# INA228.net
KiCad netlist of a schematic drawn in Altium Designer
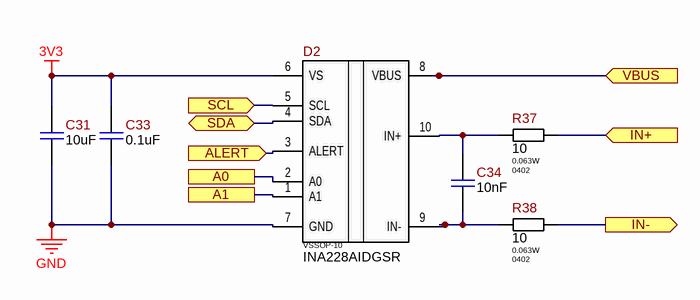
[diagram p0: INA228.SchDoc]

(export (version "E")
  (design (tool "Eeschema 10.0.6"))
  (components
    (comp (ref "C31")
      (value "10uF")
      (footprint "C0402(1005)")
      (description "CAP CER 10UF 6.3V X6S 0402")
      (fields (field (name "PART NUMBER") "10uF  6.3V C0402") (field (name "TOLERANCE") "±20%"))
      (libsource (lib "Database") (part "Capacitor_Ceramic"))
    )
    (comp (ref "C33")
      (value "0.1uF")
      (footprint "C0402(1005)")
      (description "CAP CER 0.1UF 25V X7R 0603")
      (fields (field (name "PART NUMBER") "0.1uF  25V C0403") (field (name "TOLERANCE") "±10%"))
      (libsource (lib "Database") (part "Capacitor_Ceramic"))
    )
    (comp (ref "C34")
      (value "10nF")
      (footprint "C0402(1005)")
      (description "CAP CER 10NF 50V NP0 0603")
      (fields (field (name "PART NUMBER") "10nF  50V C0402") (field (name "TOLERANCE") "±0.25pF"))
      (libsource (lib "Database") (part "Capacitor_Ceramic"))
    )
    (comp (ref "D2")
      (value "INA228AIDGSR")
      (footprint "TI-VSSOP-10-50P490X110")
      (description "85V, 20Bit, Ultra-Precise Power/Energy/Charge Monitor With I2C, 2.7V to 5.5V Supply, VSSOP-10")
      (fields
        (field (name "PACKAGE") "VSSOP-10")
        (field (name "PART NUMBER") "INA228AIDGSR")
        (field (name "MANUFACTURER") "Texas Instruments")
      )
      (libsource (lib "AjaxLibrary") (part "INA228AxDGS"))
    )
    (comp (ref "R37")
      (value "10")
      (footprint "R0402")
      (description "RES SMD 10 OHM  ±1% 1/16W 0402")
      (fields
        (field (name "POWER RATING") "0.063W")
        (field (name "PACKAGE/CASE") "0402")
        (field (name "PART NUMBER") "10  R0402")
        (field (name "TOLERANCE") "±1%")
      )
      (libsource (lib "Database") (part "R0402"))
    )
    (comp (ref "R38")
      (value "10")
      (footprint "R0402")
      (description "RES SMD 10 OHM  ±1% 1/16W 0402")
      (fields
        (field (name "POWER RATING") "0.063W")
        (field (name "PACKAGE/CASE") "0402")
        (field (name "PART NUMBER") "10  R0402")
        (field (name "TOLERANCE") "±1%")
      )
      (libsource (lib "Database") (part "R0402"))
    )
  )
  (nets
    (net (code "1") (name "/A0") (class "Default")
      (node (ref "D2") (pin "2") (pinfunction "A0_2") (pintype "passive"))
    )
    (net (code "2") (name "/A1") (class "Default")
      (node (ref "D2") (pin "1") (pinfunction "A1_1") (pintype "passive"))
    )
    (net (code "3") (name "/ALERT") (class "Default")
      (node (ref "D2") (pin "3") (pinfunction "ALERT_3") (pintype "passive"))
    )
    (net (code "4") (name "/IN+") (class "Default")
      (node (ref "R37") (pin "2") (pinfunction "2_2") (pintype "passive"))
    )
    (net (code "5") (name "/IN-") (class "Default")
      (node (ref "R38") (pin "2") (pinfunction "2_2") (pintype "passive"))
    )
    (net (code "6") (name "/SCL") (class "Default")
      (node (ref "D2") (pin "5") (pinfunction "SCL_5") (pintype "passive"))
    )
    (net (code "7") (name "/SDA") (class "Default")
      (node (ref "D2") (pin "4") (pinfunction "SDA_4") (pintype "passive"))
    )
    (net (code "8") (name "/VBUS") (class "Default")
      (node (ref "D2") (pin "8") (pinfunction "VBUS_8") (pintype "passive"))
    )
    (net (code "9") (name "3V3") (class "Default")
      (node (ref "C31") (pin "2") (pinfunction "2_2") (pintype "passive"))
      (node (ref "C33") (pin "2") (pinfunction "2_2") (pintype "passive"))
      (node (ref "D2") (pin "6") (pinfunction "VS_6") (pintype "passive"))
    )
    (net (code "10") (name "GND") (class "Default")
      (node (ref "C31") (pin "1") (pinfunction "1_1") (pintype "passive"))
      (node (ref "C33") (pin "1") (pinfunction "1_1") (pintype "passive"))
      (node (ref "D2") (pin "7") (pinfunction "GND_7") (pintype "passive"))
    )
    (net (code "11") (name "Net-(D2-IN+)") (class "Default")
      (node (ref "C34") (pin "2") (pinfunction "2_2") (pintype "passive"))
      (node (ref "D2") (pin "10") (pinfunction "IN+_10") (pintype "passive"))
      (node (ref "R37") (pin "1") (pinfunction "1_1") (pintype "passive"))
    )
    (net (code "12") (name "Net-(D2-IN-)") (class "Default")
      (node (ref "C34") (pin "1") (pinfunction "1_1") (pintype "passive"))
      (node (ref "D2") (pin "9") (pinfunction "IN-_9") (pintype "passive"))
      (node (ref "R38") (pin "1") (pinfunction "1_1") (pintype "passive"))
    )
  )
)
